# ecg.net
KiCad netlist of a schematic drawn in EAGLE
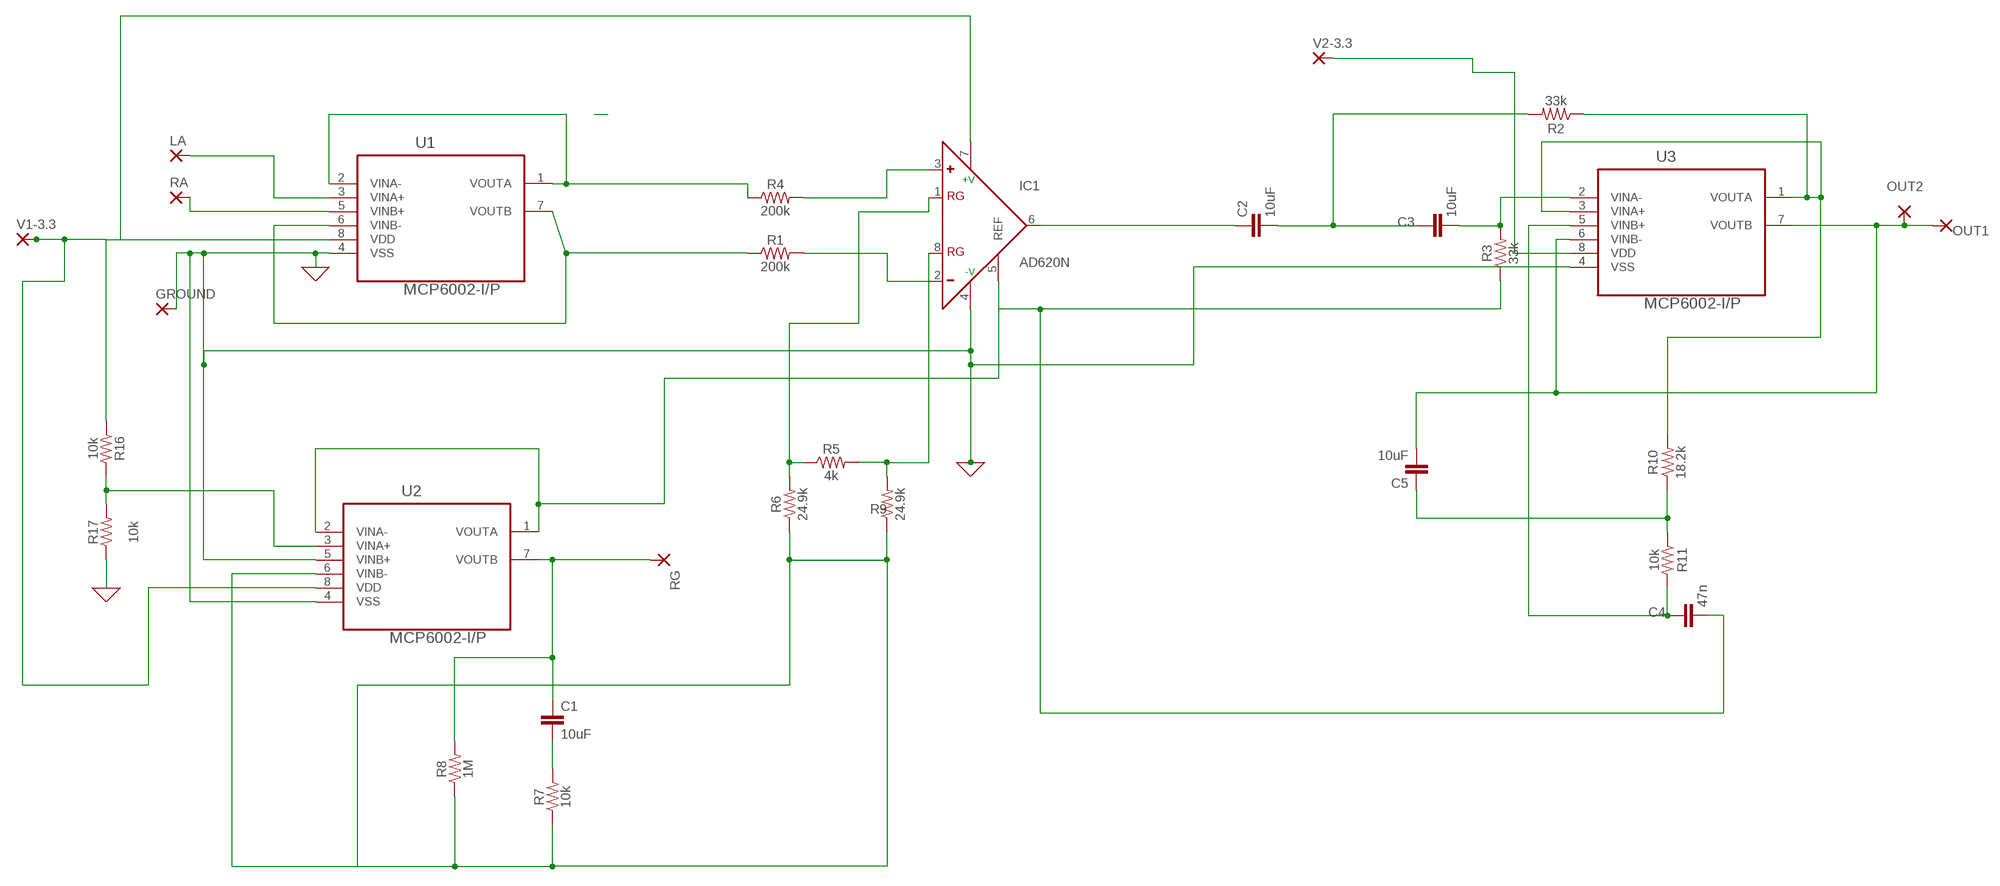
[diagram p0: schematic, sheet 1]

(export (version "E")
  (design (tool "Eeschema 10.0.6"))
  (components
    (comp (ref "C1")
      (value "10uF")
      (footprint "eagle-import:CAP-PTH-SMALL-KIT")
      (libsource (lib "eagle-import") (part "0.1UF-KIT-EZ-50V-20%"))
    )
    (comp (ref "C2")
      (value "10uF")
      (footprint "eagle-import:CAP-PTH-SMALL-KIT")
      (libsource (lib "eagle-import") (part "0.1UF-KIT-EZ-50V-20%"))
    )
    (comp (ref "C3")
      (value "10uF")
      (footprint "eagle-import:CAP-PTH-SMALL-KIT")
      (libsource (lib "eagle-import") (part "0.1UF-KIT-EZ-50V-20%"))
    )
    (comp (ref "C4")
      (value "47n")
      (footprint "eagle-import:CAP-PTH-SMALL-KIT")
      (libsource (lib "eagle-import") (part "0.1UF-KIT-EZ-50V-20%"))
    )
    (comp (ref "C5")
      (value "10uF")
      (footprint "eagle-import:CAP-PTH-SMALL-KIT")
      (libsource (lib "eagle-import") (part "0.1UF-KIT-EZ-50V-20%"))
    )
    (comp (ref "GROUND")
      (value "3,81/1,4")
      (footprint "eagle-import:3,81_1,4")
      (libsource (lib "eagle-import") (part "3,81/1,4"))
    )
    (comp (ref "IC1")
      (value "AD620N")
      (footprint "eagle-import:DIL08")
      (fields (field (name "MF") "ALTERA CORPORATION") (field (name "MPN") "AD620AN"))
      (libsource (lib "eagle-import") (part "AD620N"))
    )
    (comp (ref "LA")
      (value "3,81/1,4")
      (footprint "eagle-import:3,81_1,4")
      (libsource (lib "eagle-import") (part "3,81/1,4"))
    )
    (comp (ref "OUT1")
      (value "3,81/1,4")
      (footprint "eagle-import:3,81_1,4")
      (libsource (lib "eagle-import") (part "3,81/1,4"))
    )
    (comp (ref "OUT2")
      (value "3,81/1,4")
      (footprint "eagle-import:3,81_1,4")
      (libsource (lib "eagle-import") (part "3,81/1,4"))
    )
    (comp (ref "R1")
      (value "200k")
      (footprint "eagle-import:AXIAL-0.3")
      (libsource (lib "eagle-import") (part "15KOHM-HORIZ-1/4W-5%"))
    )
    (comp (ref "R2")
      (value "33k")
      (footprint "eagle-import:AXIAL-0.3")
      (libsource (lib "eagle-import") (part "15KOHM-HORIZ-1/4W-5%"))
    )
    (comp (ref "R3")
      (value "33k")
      (footprint "eagle-import:AXIAL-0.3")
      (libsource (lib "eagle-import") (part "15KOHM-HORIZ-1/4W-5%"))
    )
    (comp (ref "R4")
      (value "200k")
      (footprint "eagle-import:AXIAL-0.3")
      (libsource (lib "eagle-import") (part "15KOHM-HORIZ-1/4W-5%"))
    )
    (comp (ref "R5")
      (value "4k")
      (footprint "eagle-import:AXIAL-0.3")
      (libsource (lib "eagle-import") (part "15KOHM-HORIZ-1/4W-5%"))
    )
    (comp (ref "R6")
      (value "24.9k")
      (footprint "eagle-import:AXIAL-0.3")
      (libsource (lib "eagle-import") (part "15KOHM-HORIZ-1/4W-5%"))
    )
    (comp (ref "R7")
      (value "10k")
      (footprint "eagle-import:AXIAL-0.3")
      (libsource (lib "eagle-import") (part "15KOHM-HORIZ-1/4W-5%"))
    )
    (comp (ref "R8")
      (value "1M")
      (footprint "eagle-import:AXIAL-0.3")
      (libsource (lib "eagle-import") (part "15KOHM-HORIZ-1/4W-5%"))
    )
    (comp (ref "R9")
      (value "24.9k")
      (footprint "eagle-import:AXIAL-0.3")
      (libsource (lib "eagle-import") (part "15KOHM-HORIZ-1/4W-5%"))
    )
    (comp (ref "R10")
      (value "18.2k")
      (footprint "eagle-import:AXIAL-0.3")
      (libsource (lib "eagle-import") (part "15KOHM-HORIZ-1/4W-5%"))
    )
    (comp (ref "R11")
      (value "10k")
      (footprint "eagle-import:AXIAL-0.3")
      (libsource (lib "eagle-import") (part "15KOHM-HORIZ-1/4W-5%"))
    )
    (comp (ref "R16")
      (value "10k")
      (footprint "eagle-import:AXIAL-0.3")
      (libsource (lib "eagle-import") (part "15KOHM-HORIZ-1/4W-5%"))
    )
    (comp (ref "R17")
      (value "10k")
      (footprint "eagle-import:AXIAL-0.3")
      (libsource (lib "eagle-import") (part "15KOHM-HORIZ-1/4W-5%"))
    )
    (comp (ref "RA")
      (value "3,81/1,4")
      (footprint "eagle-import:3,81_1,4")
      (libsource (lib "eagle-import") (part "3,81/1,4"))
    )
    (comp (ref "RG")
      (value "3,81/1,4")
      (footprint "eagle-import:3,81_1,4")
      (libsource (lib "eagle-import") (part "3,81/1,4"))
    )
    (comp (ref "U1")
      (value "MCP6002-I/P")
      (footprint "eagle-import:DIP254P762X533-8")
      (fields (field (name "DIGI-KEY_PART_NUMBER") "MCP6002-I/P-ND") (field (name "MF") "Microchip"))
      (libsource (lib "eagle-import") (part "MCP6002-I/P"))
    )
    (comp (ref "U2")
      (value "MCP6002-I/P")
      (footprint "eagle-import:DIP254P762X533-8")
      (fields (field (name "DIGI-KEY_PART_NUMBER") "MCP6002-I/P-ND") (field (name "MF") "Microchip"))
      (libsource (lib "eagle-import") (part "MCP6002-I/P"))
    )
    (comp (ref "U3")
      (value "MCP6002-I/P")
      (footprint "eagle-import:DIP254P762X533-8")
      (fields (field (name "DIGI-KEY_PART_NUMBER") "MCP6002-I/P-ND") (field (name "MF") "Microchip"))
      (libsource (lib "eagle-import") (part "MCP6002-I/P"))
    )
    (comp (ref "V1-3.3")
      (value "3,81/1,4")
      (footprint "eagle-import:3,81_1,4")
      (libsource (lib "eagle-import") (part "3,81/1,4"))
    )
    (comp (ref "V2-3.3")
      (value "3,81/1,4")
      (footprint "eagle-import:3,81_1,4")
      (libsource (lib "eagle-import") (part "3,81/1,4"))
    )
  )
  (nets
    (net (code "1") (name "GND") (class "Default")
      (node (ref "GROUND") (pin "1") (pinfunction "P_1") (pintype "passive"))
      (node (ref "IC1") (pin "4") (pinfunction "-V_4") (pintype "power_in"))
      (node (ref "R17") (pin "P$1") (pinfunction "1_P$1") (pintype "passive"))
      (node (ref "U1") (pin "4") (pinfunction "VSS_4") (pintype "passive"))
      (node (ref "U2") (pin "4") (pinfunction "VSS_4") (pintype "passive"))
      (node (ref "U2") (pin "5") (pinfunction "VINB+_5") (pintype "input"))
      (node (ref "U3") (pin "4") (pinfunction "VSS_4") (pintype "passive"))
    )
    (net (code "2") (name "Net-(IC1-+)") (class "Default")
      (node (ref "IC1") (pin "3") (pinfunction "+_3") (pintype "input"))
      (node (ref "R4") (pin "P$2") (pinfunction "2_P$2") (pintype "passive"))
    )
    (net (code "3") (name "Net-(IC1-+V)") (class "Default")
      (node (ref "IC1") (pin "7") (pinfunction "+V_7") (pintype "power_in"))
      (node (ref "R16") (pin "P$1") (pinfunction "1_P$1") (pintype "passive"))
      (node (ref "U1") (pin "8") (pinfunction "VDD_8") (pintype "power_in"))
      (node (ref "U2") (pin "8") (pinfunction "VDD_8") (pintype "power_in"))
      (node (ref "V1-3.3") (pin "1") (pinfunction "P_1") (pintype "passive"))
    )
    (net (code "4") (name "Net-(IC1--)") (class "Default")
      (node (ref "IC1") (pin "2") (pinfunction "-_2") (pintype "input"))
      (node (ref "R1") (pin "P$2") (pinfunction "2_P$2") (pintype "passive"))
    )
    (net (code "5") (name "Net-(IC1-OUT)") (class "Default")
      (node (ref "C2") (pin "1") (pinfunction "1_1") (pintype "passive"))
      (node (ref "IC1") (pin "6") (pinfunction "OUT_6") (pintype "output"))
    )
    (net (code "6") (name "Net-(IC1-REF)") (class "Default")
      (node (ref "C4") (pin "2") (pinfunction "2_2") (pintype "passive"))
      (node (ref "IC1") (pin "5") (pinfunction "REF_5") (pintype "passive"))
      (node (ref "R3") (pin "P$1") (pinfunction "1_P$1") (pintype "passive"))
      (node (ref "U2") (pin "1") (pinfunction "VOUTA_1") (pintype "output"))
      (node (ref "U2") (pin "2") (pinfunction "VINA-_2") (pintype "input"))
    )
    (net (code "7") (name "Net-(LA-P)") (class "Default")
      (node (ref "LA") (pin "1") (pinfunction "P_1") (pintype "passive"))
      (node (ref "U1") (pin "3") (pinfunction "VINA+_3") (pintype "input"))
    )
    (net (code "8") (name "Net-(OUT1-P)") (class "Default")
      (node (ref "C5") (pin "2") (pinfunction "2_2") (pintype "passive"))
      (node (ref "OUT1") (pin "1") (pinfunction "P_1") (pintype "passive"))
      (node (ref "OUT2") (pin "1") (pinfunction "P_1") (pintype "passive"))
      (node (ref "U3") (pin "6") (pinfunction "VINB-_6") (pintype "input"))
      (node (ref "U3") (pin "7") (pinfunction "VOUTB_7") (pintype "output"))
    )
    (net (code "9") (name "Net-(R1-1)") (class "Default")
      (node (ref "R1") (pin "P$1") (pinfunction "1_P$1") (pintype "passive"))
      (node (ref "U1") (pin "6") (pinfunction "VINB-_6") (pintype "input"))
      (node (ref "U1") (pin "7") (pinfunction "VOUTB_7") (pintype "output"))
    )
    (net (code "10") (name "Net-(R2-2)") (class "Default")
      (node (ref "C2") (pin "2") (pinfunction "2_2") (pintype "passive"))
      (node (ref "C3") (pin "1") (pinfunction "1_1") (pintype "passive"))
      (node (ref "R2") (pin "P$2") (pinfunction "2_P$2") (pintype "passive"))
    )
    (net (code "11") (name "Net-(R3-2)") (class "Default")
      (node (ref "C3") (pin "2") (pinfunction "2_2") (pintype "passive"))
      (node (ref "R3") (pin "P$2") (pinfunction "2_P$2") (pintype "passive"))
      (node (ref "U3") (pin "2") (pinfunction "VINA-_2") (pintype "input"))
    )
    (net (code "12") (name "Net-(R4-1)") (class "Default")
      (node (ref "R4") (pin "P$1") (pinfunction "1_P$1") (pintype "passive"))
      (node (ref "U1") (pin "1") (pinfunction "VOUTA_1") (pintype "output"))
      (node (ref "U1") (pin "2") (pinfunction "VINA-_2") (pintype "input"))
    )
    (net (code "13") (name "Net-(R5-1)") (class "Default")
      (node (ref "IC1") (pin "1") (pinfunction "RG_1") (pintype "passive"))
      (node (ref "R5") (pin "P$1") (pinfunction "1_P$1") (pintype "passive"))
      (node (ref "R6") (pin "P$2") (pinfunction "2_P$2") (pintype "passive"))
    )
    (net (code "14") (name "Net-(R5-2)") (class "Default")
      (node (ref "IC1") (pin "8") (pinfunction "RG_8") (pintype "passive"))
      (node (ref "R5") (pin "P$2") (pinfunction "2_P$2") (pintype "passive"))
      (node (ref "R9") (pin "P$2") (pinfunction "2_P$2") (pintype "passive"))
    )
    (net (code "15") (name "Net-(R6-1)") (class "Default")
      (node (ref "R6") (pin "P$1") (pinfunction "1_P$1") (pintype "passive"))
      (node (ref "R7") (pin "P$1") (pinfunction "1_P$1") (pintype "passive"))
      (node (ref "R8") (pin "P$1") (pinfunction "1_P$1") (pintype "passive"))
      (node (ref "R9") (pin "P$1") (pinfunction "1_P$1") (pintype "passive"))
      (node (ref "U2") (pin "6") (pinfunction "VINB-_6") (pintype "input"))
    )
    (net (code "16") (name "Net-(R7-2)") (class "Default")
      (node (ref "C1") (pin "2") (pinfunction "2_2") (pintype "passive"))
      (node (ref "R7") (pin "P$2") (pinfunction "2_P$2") (pintype "passive"))
    )
    (net (code "17") (name "Net-(R8-2)") (class "Default")
      (node (ref "C1") (pin "1") (pinfunction "1_1") (pintype "passive"))
      (node (ref "R8") (pin "P$2") (pinfunction "2_P$2") (pintype "passive"))
      (node (ref "RG") (pin "1") (pinfunction "P_1") (pintype "passive"))
      (node (ref "U2") (pin "7") (pinfunction "VOUTB_7") (pintype "output"))
    )
    (net (code "18") (name "Net-(R10-1)") (class "Default")
      (node (ref "C5") (pin "1") (pinfunction "1_1") (pintype "passive"))
      (node (ref "R10") (pin "P$1") (pinfunction "1_P$1") (pintype "passive"))
      (node (ref "R11") (pin "P$1") (pinfunction "1_P$1") (pintype "passive"))
    )
    (net (code "19") (name "Net-(R10-2)") (class "Default")
      (node (ref "R10") (pin "P$2") (pinfunction "2_P$2") (pintype "passive"))
      (node (ref "R2") (pin "P$1") (pinfunction "1_P$1") (pintype "passive"))
      (node (ref "U3") (pin "1") (pinfunction "VOUTA_1") (pintype "output"))
      (node (ref "U3") (pin "3") (pinfunction "VINA+_3") (pintype "input"))
    )
    (net (code "20") (name "Net-(R11-2)") (class "Default")
      (node (ref "C4") (pin "1") (pinfunction "1_1") (pintype "passive"))
      (node (ref "R11") (pin "P$2") (pinfunction "2_P$2") (pintype "passive"))
      (node (ref "U3") (pin "5") (pinfunction "VINB+_5") (pintype "input"))
    )
    (net (code "21") (name "Net-(R16-2)") (class "Default")
      (node (ref "R16") (pin "P$2") (pinfunction "2_P$2") (pintype "passive"))
      (node (ref "R17") (pin "P$2") (pinfunction "2_P$2") (pintype "passive"))
      (node (ref "U2") (pin "3") (pinfunction "VINA+_3") (pintype "input"))
    )
    (net (code "22") (name "Net-(RA-P)") (class "Default")
      (node (ref "RA") (pin "1") (pinfunction "P_1") (pintype "passive"))
      (node (ref "U1") (pin "5") (pinfunction "VINB+_5") (pintype "input"))
    )
    (net (code "23") (name "Net-(U3-VDD)") (class "Default")
      (node (ref "U3") (pin "8") (pinfunction "VDD_8") (pintype "power_in"))
      (node (ref "V2-3.3") (pin "1") (pinfunction "P_1") (pintype "passive"))
    )
  )
)
